# photoresistor-array.net
KiCad netlist of a schematic drawn in EAGLE
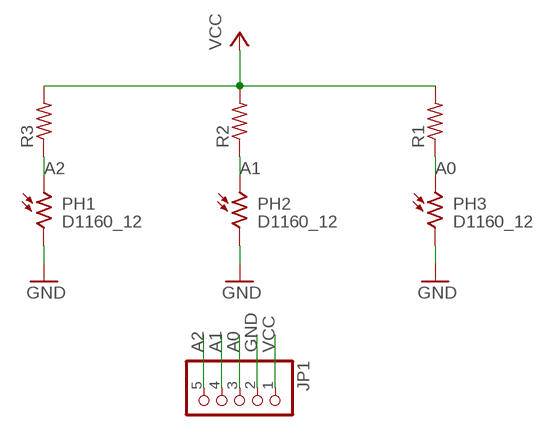
[diagram p0: schematic, sheet 1]

(export (version "E")
  (design (tool "Eeschema 10.0.6"))
  (components
    (comp (ref "JP1")
      (value "PINHD-1X5")
      (footprint "eagle-import:1X05")
      (libsource (lib "eagle-import") (part "PINHD-1X5"))
    )
    (comp (ref "PH1")
      (value "D1160_12")
      (footprint "eagle-import:D11XX")
      (libsource (lib "eagle-import") (part "D1160_12"))
    )
    (comp (ref "PH2")
      (value "D1160_12")
      (footprint "eagle-import:D11XX")
      (libsource (lib "eagle-import") (part "D1160_12"))
    )
    (comp (ref "PH3")
      (value "D1160_12")
      (footprint "eagle-import:D11XX")
      (libsource (lib "eagle-import") (part "D1160_12"))
    )
    (comp (ref "R1")
      (value "R-US_0207/10")
      (footprint "eagle-import:0207_10")
      (libsource (lib "eagle-import") (part "R-US_0207/10"))
    )
    (comp (ref "R2")
      (value "R-US_0207/10")
      (footprint "eagle-import:0207_10")
      (libsource (lib "eagle-import") (part "R-US_0207/10"))
    )
    (comp (ref "R3")
      (value "R-US_0207/10")
      (footprint "eagle-import:0207_10")
      (libsource (lib "eagle-import") (part "R-US_0207/10"))
    )
  )
  (nets
    (net (code "1") (name "/A0") (class "Default")
      (node (ref "JP1") (pin "3") (pinfunction "3_3") (pintype "passive"))
      (node (ref "PH3") (pin "1") (pinfunction "1_1") (pintype "passive"))
      (node (ref "R1") (pin "1") (pinfunction "1_1") (pintype "passive"))
    )
    (net (code "2") (name "/A1") (class "Default")
      (node (ref "JP1") (pin "4") (pinfunction "4_4") (pintype "passive"))
      (node (ref "PH2") (pin "1") (pinfunction "1_1") (pintype "passive"))
      (node (ref "R2") (pin "1") (pinfunction "1_1") (pintype "passive"))
    )
    (net (code "3") (name "/A2") (class "Default")
      (node (ref "JP1") (pin "5") (pinfunction "5_5") (pintype "passive"))
      (node (ref "PH1") (pin "1") (pinfunction "1_1") (pintype "passive"))
      (node (ref "R3") (pin "1") (pinfunction "1_1") (pintype "passive"))
    )
    (net (code "4") (name "GND") (class "Default")
      (node (ref "JP1") (pin "2") (pinfunction "2_2") (pintype "passive"))
      (node (ref "PH1") (pin "2") (pinfunction "2_2") (pintype "passive"))
      (node (ref "PH2") (pin "2") (pinfunction "2_2") (pintype "passive"))
      (node (ref "PH3") (pin "2") (pinfunction "2_2") (pintype "passive"))
    )
    (net (code "5") (name "VCC") (class "Default")
      (node (ref "JP1") (pin "1") (pinfunction "1_1") (pintype "passive"))
      (node (ref "R1") (pin "2") (pinfunction "2_2") (pintype "passive"))
      (node (ref "R2") (pin "2") (pinfunction "2_2") (pintype "passive"))
      (node (ref "R3") (pin "2") (pinfunction "2_2") (pintype "passive"))
    )
  )
)
